# LCD_Controller.net
KiCad netlist of a schematic drawn in Altium Designer
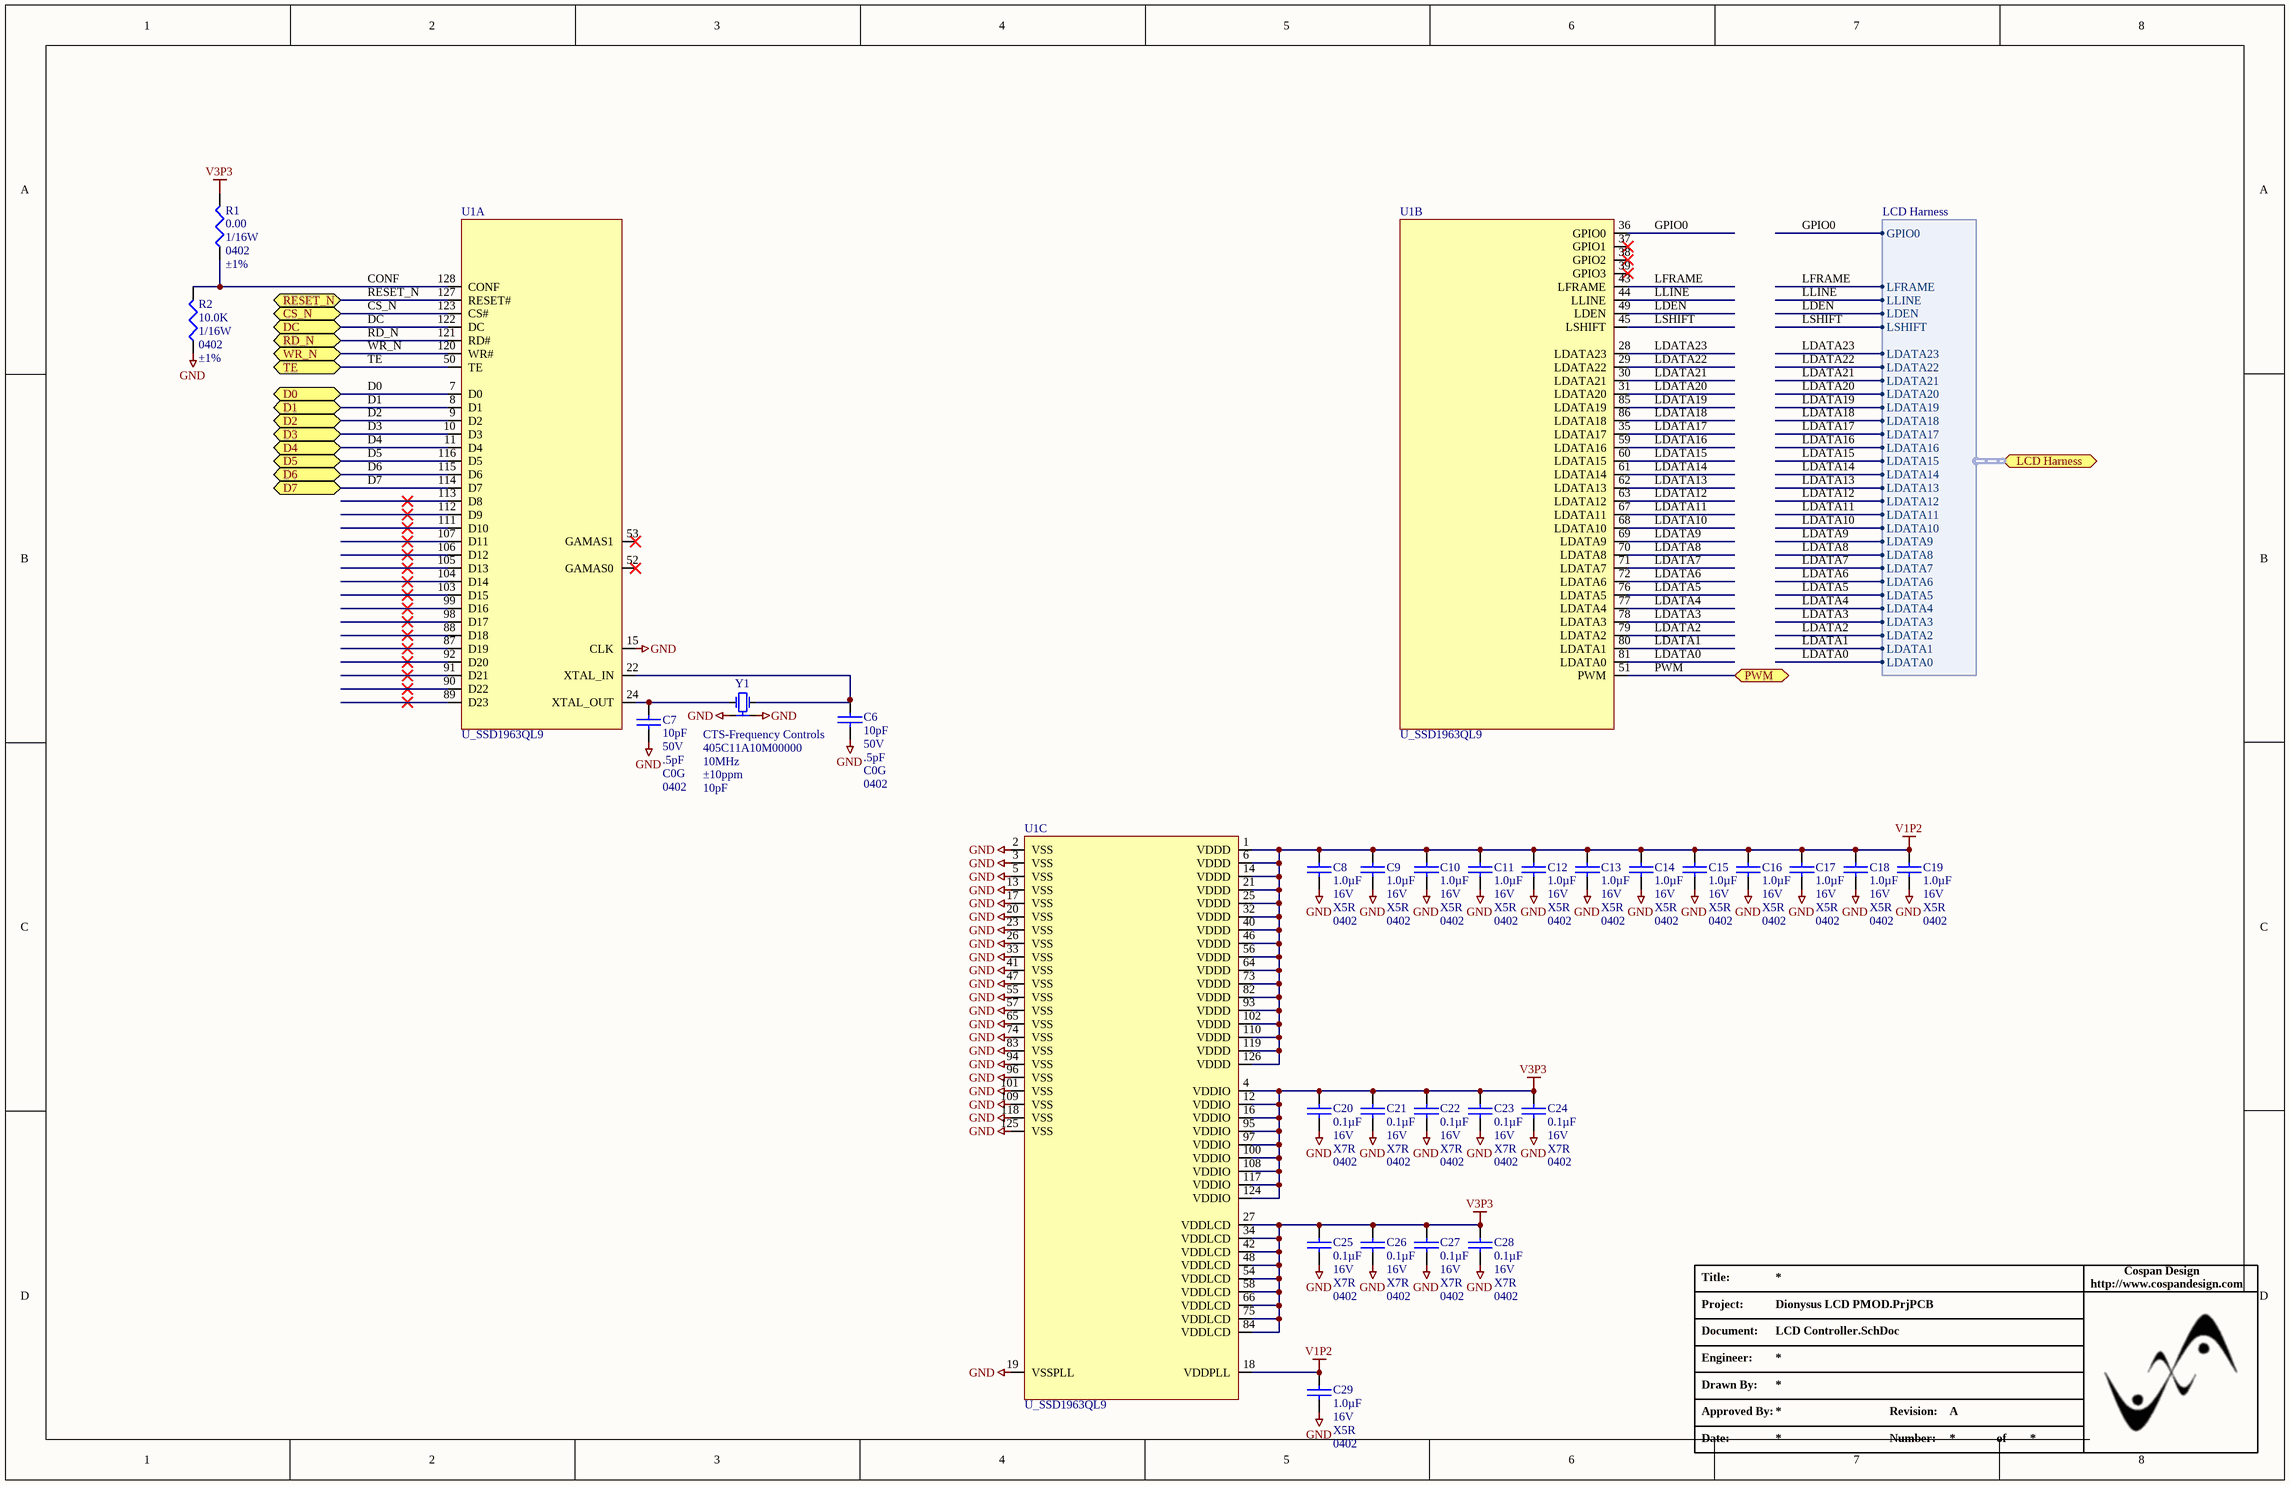
[diagram p0: LCD Controller.SchDoc]

(export (version "E")
  (design (tool "Eeschema 10.0.6"))
  (components
    (comp (ref "C6")
      (value "10pF")
      (footprint "C_ERA-0402")
      (description "CAP CER 10PF 50V NP0 0402")
      (fields
        (field (name "MANUFACTURER") "Taiyo Yuden")
        (field (name "MANUFACTURER PART NUMBER") "UMK105CG100DV-F")
        (field (name "CAPACITANCE") "10pF")
        (field (name "VOLTAGE - RATED") "50V")
        (field (name "TOLERANCE") ".5pF")
        (field (name "TEMPERATURE COEFFICIENT") "C0G")
        (field (name "PACKAGE / CASE") "0402")
      )
      (libsource (lib "Main Library") (part "C_0402_10PF_50V"))
    )
    (comp (ref "C7")
      (value "10pF")
      (footprint "C_ERA-0402")
      (description "CAP CER 10PF 50V NP0 0402")
      (fields
        (field (name "MANUFACTURER") "Taiyo Yuden")
        (field (name "MANUFACTURER PART NUMBER") "UMK105CG100DV-F")
        (field (name "CAPACITANCE") "10pF")
        (field (name "VOLTAGE - RATED") "50V")
        (field (name "TOLERANCE") ".5pF")
        (field (name "TEMPERATURE COEFFICIENT") "C0G")
        (field (name "PACKAGE / CASE") "0402")
      )
      (libsource (lib "Main Library") (part "C_0402_10PF_50V"))
    )
    (comp (ref "C8")
      (value "1.0uF")
      (footprint "C_ERA-0402")
      (description "CAP CER 1.0UF 16V X5R 0402")
      (fields
        (field (name "TOLERANCE") "±10%")
        (field (name "MANUFACTURER") "TDK Corporation")
        (field (name "CAPACITANCE") "1.0µF")
        (field (name "VOLTAGE - RATED") "16V")
        (field (name "TEMPERATURE COEFFICIENT") "X5R")
        (field (name "PACKAGE / CASE") "0402")
      )
      (libsource (lib "Main Library") (part "C_0402_1.0UF_16V"))
    )
    (comp (ref "C9")
      (value "1.0uF")
      (footprint "C_ERA-0402")
      (description "CAP CER 1.0UF 16V X5R 0402")
      (fields
        (field (name "TOLERANCE") "±10%")
        (field (name "MANUFACTURER") "TDK Corporation")
        (field (name "CAPACITANCE") "1.0µF")
        (field (name "VOLTAGE - RATED") "16V")
        (field (name "TEMPERATURE COEFFICIENT") "X5R")
        (field (name "PACKAGE / CASE") "0402")
      )
      (libsource (lib "Main Library") (part "C_0402_1.0UF_16V"))
    )
    (comp (ref "C10")
      (value "1.0uF")
      (footprint "C_ERA-0402")
      (description "CAP CER 1.0UF 16V X5R 0402")
      (fields
        (field (name "TOLERANCE") "±10%")
        (field (name "MANUFACTURER") "TDK Corporation")
        (field (name "CAPACITANCE") "1.0µF")
        (field (name "VOLTAGE - RATED") "16V")
        (field (name "TEMPERATURE COEFFICIENT") "X5R")
        (field (name "PACKAGE / CASE") "0402")
      )
      (libsource (lib "Main Library") (part "C_0402_1.0UF_16V"))
    )
    (comp (ref "C11")
      (value "1.0uF")
      (footprint "C_ERA-0402")
      (description "CAP CER 1.0UF 16V X5R 0402")
      (fields
        (field (name "TOLERANCE") "±10%")
        (field (name "MANUFACTURER") "TDK Corporation")
        (field (name "CAPACITANCE") "1.0µF")
        (field (name "VOLTAGE - RATED") "16V")
        (field (name "TEMPERATURE COEFFICIENT") "X5R")
        (field (name "PACKAGE / CASE") "0402")
      )
      (libsource (lib "Main Library") (part "C_0402_1.0UF_16V"))
    )
    (comp (ref "C12")
      (value "1.0uF")
      (footprint "C_ERA-0402")
      (description "CAP CER 1.0UF 16V X5R 0402")
      (fields
        (field (name "TOLERANCE") "±10%")
        (field (name "MANUFACTURER") "TDK Corporation")
        (field (name "CAPACITANCE") "1.0µF")
        (field (name "VOLTAGE - RATED") "16V")
        (field (name "TEMPERATURE COEFFICIENT") "X5R")
        (field (name "PACKAGE / CASE") "0402")
      )
      (libsource (lib "Main Library") (part "C_0402_1.0UF_16V"))
    )
    (comp (ref "C13")
      (value "1.0uF")
      (footprint "C_ERA-0402")
      (description "CAP CER 1.0UF 16V X5R 0402")
      (fields
        (field (name "TOLERANCE") "±10%")
        (field (name "MANUFACTURER") "TDK Corporation")
        (field (name "CAPACITANCE") "1.0µF")
        (field (name "VOLTAGE - RATED") "16V")
        (field (name "TEMPERATURE COEFFICIENT") "X5R")
        (field (name "PACKAGE / CASE") "0402")
      )
      (libsource (lib "Main Library") (part "C_0402_1.0UF_16V"))
    )
    (comp (ref "C14")
      (value "1.0uF")
      (footprint "C_ERA-0402")
      (description "CAP CER 1.0UF 16V X5R 0402")
      (fields
        (field (name "TOLERANCE") "±10%")
        (field (name "MANUFACTURER") "TDK Corporation")
        (field (name "CAPACITANCE") "1.0µF")
        (field (name "VOLTAGE - RATED") "16V")
        (field (name "TEMPERATURE COEFFICIENT") "X5R")
        (field (name "PACKAGE / CASE") "0402")
      )
      (libsource (lib "Main Library") (part "C_0402_1.0UF_16V"))
    )
    (comp (ref "C15")
      (value "1.0uF")
      (footprint "C_ERA-0402")
      (description "CAP CER 1.0UF 16V X5R 0402")
      (fields
        (field (name "TOLERANCE") "±10%")
        (field (name "MANUFACTURER") "TDK Corporation")
        (field (name "CAPACITANCE") "1.0µF")
        (field (name "VOLTAGE - RATED") "16V")
        (field (name "TEMPERATURE COEFFICIENT") "X5R")
        (field (name "PACKAGE / CASE") "0402")
      )
      (libsource (lib "Main Library") (part "C_0402_1.0UF_16V"))
    )
    (comp (ref "C16")
      (value "1.0uF")
      (footprint "C_ERA-0402")
      (description "CAP CER 1.0UF 16V X5R 0402")
      (fields
        (field (name "TOLERANCE") "±10%")
        (field (name "MANUFACTURER") "TDK Corporation")
        (field (name "CAPACITANCE") "1.0µF")
        (field (name "VOLTAGE - RATED") "16V")
        (field (name "TEMPERATURE COEFFICIENT") "X5R")
        (field (name "PACKAGE / CASE") "0402")
      )
      (libsource (lib "Main Library") (part "C_0402_1.0UF_16V"))
    )
    (comp (ref "C17")
      (value "1.0uF")
      (footprint "C_ERA-0402")
      (description "CAP CER 1.0UF 16V X5R 0402")
      (fields
        (field (name "TOLERANCE") "±10%")
        (field (name "MANUFACTURER") "TDK Corporation")
        (field (name "CAPACITANCE") "1.0µF")
        (field (name "VOLTAGE - RATED") "16V")
        (field (name "TEMPERATURE COEFFICIENT") "X5R")
        (field (name "PACKAGE / CASE") "0402")
      )
      (libsource (lib "Main Library") (part "C_0402_1.0UF_16V"))
    )
    (comp (ref "C18")
      (value "1.0uF")
      (footprint "C_ERA-0402")
      (description "CAP CER 1.0UF 16V X5R 0402")
      (fields
        (field (name "TOLERANCE") "±10%")
        (field (name "MANUFACTURER") "TDK Corporation")
        (field (name "CAPACITANCE") "1.0µF")
        (field (name "VOLTAGE - RATED") "16V")
        (field (name "TEMPERATURE COEFFICIENT") "X5R")
        (field (name "PACKAGE / CASE") "0402")
      )
      (libsource (lib "Main Library") (part "C_0402_1.0UF_16V"))
    )
    (comp (ref "C19")
      (value "1.0uF")
      (footprint "C_ERA-0402")
      (description "CAP CER 1.0UF 16V X5R 0402")
      (fields
        (field (name "TOLERANCE") "±10%")
        (field (name "MANUFACTURER") "TDK Corporation")
        (field (name "CAPACITANCE") "1.0µF")
        (field (name "VOLTAGE - RATED") "16V")
        (field (name "TEMPERATURE COEFFICIENT") "X5R")
        (field (name "PACKAGE / CASE") "0402")
      )
      (libsource (lib "Main Library") (part "C_0402_1.0UF_16V"))
    )
    (comp (ref "C20")
      (value "0.1uF")
      (footprint "C_0402")
      (description "CAP CER .10UF 16V X7R 0402")
      (fields
        (field (name "MANUFACTURER") "TDK Corporation")
        (field (name "MANUFACTURER PART NUMBER") "C1005X7R1C104K")
        (field (name "CAPACITANCE") "0.1µF")
        (field (name "VOLTAGE - RATED") "16V")
        (field (name "TEMPERATURE COEFFICIENT") "X7R")
        (field (name "PACKAGE / CASE") "0402")
      )
      (libsource (lib "Main Library") (part "C_0402_0.1UF_16V"))
    )
    (comp (ref "C21")
      (value "0.1uF")
      (footprint "C_0402")
      (description "CAP CER .10UF 16V X7R 0402")
      (fields
        (field (name "MANUFACTURER") "TDK Corporation")
        (field (name "MANUFACTURER PART NUMBER") "C1005X7R1C104K")
        (field (name "CAPACITANCE") "0.1µF")
        (field (name "VOLTAGE - RATED") "16V")
        (field (name "TEMPERATURE COEFFICIENT") "X7R")
        (field (name "PACKAGE / CASE") "0402")
      )
      (libsource (lib "Main Library") (part "C_0402_0.1UF_16V"))
    )
    (comp (ref "C22")
      (value "0.1uF")
      (footprint "C_0402")
      (description "CAP CER .10UF 16V X7R 0402")
      (fields
        (field (name "MANUFACTURER") "TDK Corporation")
        (field (name "MANUFACTURER PART NUMBER") "C1005X7R1C104K")
        (field (name "CAPACITANCE") "0.1µF")
        (field (name "VOLTAGE - RATED") "16V")
        (field (name "TEMPERATURE COEFFICIENT") "X7R")
        (field (name "PACKAGE / CASE") "0402")
      )
      (libsource (lib "Main Library") (part "C_0402_0.1UF_16V"))
    )
    (comp (ref "C23")
      (value "0.1uF")
      (footprint "C_0402")
      (description "CAP CER .10UF 16V X7R 0402")
      (fields
        (field (name "MANUFACTURER") "TDK Corporation")
        (field (name "MANUFACTURER PART NUMBER") "C1005X7R1C104K")
        (field (name "CAPACITANCE") "0.1µF")
        (field (name "VOLTAGE - RATED") "16V")
        (field (name "TEMPERATURE COEFFICIENT") "X7R")
        (field (name "PACKAGE / CASE") "0402")
      )
      (libsource (lib "Main Library") (part "C_0402_0.1UF_16V"))
    )
    (comp (ref "C24")
      (value "0.1uF")
      (footprint "C_0402")
      (description "CAP CER .10UF 16V X7R 0402")
      (fields
        (field (name "MANUFACTURER") "TDK Corporation")
        (field (name "MANUFACTURER PART NUMBER") "C1005X7R1C104K")
        (field (name "CAPACITANCE") "0.1µF")
        (field (name "VOLTAGE - RATED") "16V")
        (field (name "TEMPERATURE COEFFICIENT") "X7R")
        (field (name "PACKAGE / CASE") "0402")
      )
      (libsource (lib "Main Library") (part "C_0402_0.1UF_16V"))
    )
    (comp (ref "C25")
      (value "0.1uF")
      (footprint "C_0402")
      (description "CAP CER .10UF 16V X7R 0402")
      (fields
        (field (name "MANUFACTURER") "TDK Corporation")
        (field (name "MANUFACTURER PART NUMBER") "C1005X7R1C104K")
        (field (name "CAPACITANCE") "0.1µF")
        (field (name "VOLTAGE - RATED") "16V")
        (field (name "TEMPERATURE COEFFICIENT") "X7R")
        (field (name "PACKAGE / CASE") "0402")
      )
      (libsource (lib "Main Library") (part "C_0402_0.1UF_16V"))
    )
    (comp (ref "C26")
      (value "0.1uF")
      (footprint "C_0402")
      (description "CAP CER .10UF 16V X7R 0402")
      (fields
        (field (name "MANUFACTURER") "TDK Corporation")
        (field (name "MANUFACTURER PART NUMBER") "C1005X7R1C104K")
        (field (name "CAPACITANCE") "0.1µF")
        (field (name "VOLTAGE - RATED") "16V")
        (field (name "TEMPERATURE COEFFICIENT") "X7R")
        (field (name "PACKAGE / CASE") "0402")
      )
      (libsource (lib "Main Library") (part "C_0402_0.1UF_16V"))
    )
    (comp (ref "C27")
      (value "0.1uF")
      (footprint "C_0402")
      (description "CAP CER .10UF 16V X7R 0402")
      (fields
        (field (name "MANUFACTURER") "TDK Corporation")
        (field (name "MANUFACTURER PART NUMBER") "C1005X7R1C104K")
        (field (name "CAPACITANCE") "0.1µF")
        (field (name "VOLTAGE - RATED") "16V")
        (field (name "TEMPERATURE COEFFICIENT") "X7R")
        (field (name "PACKAGE / CASE") "0402")
      )
      (libsource (lib "Main Library") (part "C_0402_0.1UF_16V"))
    )
    (comp (ref "C28")
      (value "0.1uF")
      (footprint "C_0402")
      (description "CAP CER .10UF 16V X7R 0402")
      (fields
        (field (name "MANUFACTURER") "TDK Corporation")
        (field (name "MANUFACTURER PART NUMBER") "C1005X7R1C104K")
        (field (name "CAPACITANCE") "0.1µF")
        (field (name "VOLTAGE - RATED") "16V")
        (field (name "TEMPERATURE COEFFICIENT") "X7R")
        (field (name "PACKAGE / CASE") "0402")
      )
      (libsource (lib "Main Library") (part "C_0402_0.1UF_16V"))
    )
    (comp (ref "C29")
      (value "1.0uF")
      (footprint "C_ERA-0402")
      (description "CAP CER 1.0UF 16V X5R 0402")
      (fields
        (field (name "TOLERANCE") "±10%")
        (field (name "MANUFACTURER") "TDK Corporation")
        (field (name "CAPACITANCE") "1.0µF")
        (field (name "VOLTAGE - RATED") "16V")
        (field (name "TEMPERATURE COEFFICIENT") "X5R")
        (field (name "PACKAGE / CASE") "0402")
      )
      (libsource (lib "Main Library") (part "C_0402_1.0UF_16V"))
    )
    (comp (ref "R1")
      (value "0.0 Ohms")
      (footprint "R_0402")
      (description "RES 1.00 OHM 1/16W 1% 0402 SMD")
      (fields
        (field (name "MANUFACTURER") "Panasonic - ECG")
        (field (name "MANUFACTURER PART NUMBER") "ERJ-2GE0R00X")
        (field (name "RESISTANCE IN OHMS") "0.00")
        (field (name "POWER (WATTS)") "1/16W")
        (field (name "CASE") "0402")
        (field (name "TOLERANCE") "±1%")
      )
      (libsource (lib "Main Library") (part "R_0402_0.00"))
    )
    (comp (ref "R2")
      (value "R_0402_10.0K")
      (footprint "R_0402")
      (description "RES 10.0K OHM 1/16W 1% 0402 SMD")
      (fields
        (field (name "MANUFACTURER") "Stackpole Electronics Inc")
        (field (name "MANUFACTURER PART NUMBER") "RMCF0402FT10K0")
        (field (name "RESISTANCE IN OHMS") "10.0K")
        (field (name "POWER (WATTS)") "1/16W")
        (field (name "CASE") "0402")
        (field (name "TOLERANCE") "±1%")
      )
      (libsource (lib "Main Library") (part "R_0402_10.0K"))
    )
    (comp (ref "U1")
      (value "U_SSD1963QL9")
      (footprint "LQFP128")
      (description "SSD1963QL9")
      (libsource (lib "Main LibraryX") (part "U_SSD1963QL9"))
    )
    (comp (ref "Y1")
      (value "Y_SMD_10.00MHZ_10PF")
      (footprint "SMD_OSC_8MHZ")
      (description "CRYSTAL 10MHZ 10PF SMD")
      (fields
        (field (name "MANUFACTURER") "CTS-Frequency Controls")
        (field (name "MANUFACTURER PART NUMBER") "405C11A10M00000")
        (field (name "FREQUENCY") "10MHz")
        (field (name "FREQUENCY STABILITY") "±10ppm")
        (field (name "LOAD CAPACITANCE") "10pF")
      )
      (libsource (lib "Main Library") (part "Y_SMD_10.00MHZ_10PF"))
    )
  )
  (nets
    (net (code "3") (name "/CONF") (class "Default")
      (node (ref "R1") (pin "2") (pinfunction "2_2") (pintype "passive"))
      (node (ref "R2") (pin "1") (pinfunction "1_1") (pintype "passive"))
      (node (ref "U1") (pin "128") (pinfunction "CONF_128") (pintype "passive"))
    )
    (net (code "4") (name "/CS_N") (class "Default")
      (node (ref "U1") (pin "123") (pinfunction "CS#_123") (pintype "passive"))
    )
    (net (code "5") (name "/D0") (class "Default")
      (node (ref "U1") (pin "7") (pinfunction "D0_7") (pintype "passive"))
    )
    (net (code "6") (name "/D1") (class "Default")
      (node (ref "U1") (pin "8") (pinfunction "D1_8") (pintype "passive"))
    )
    (net (code "7") (name "/D2") (class "Default")
      (node (ref "U1") (pin "9") (pinfunction "D2_9") (pintype "passive"))
    )
    (net (code "8") (name "/D3") (class "Default")
      (node (ref "U1") (pin "10") (pinfunction "D3_10") (pintype "passive"))
    )
    (net (code "9") (name "/D4") (class "Default")
      (node (ref "U1") (pin "11") (pinfunction "D4_11") (pintype "passive"))
    )
    (net (code "10") (name "/D5") (class "Default")
      (node (ref "U1") (pin "116") (pinfunction "D5_116") (pintype "passive"))
    )
    (net (code "11") (name "/D6") (class "Default")
      (node (ref "U1") (pin "115") (pinfunction "D6_115") (pintype "passive"))
    )
    (net (code "12") (name "/D7") (class "Default")
      (node (ref "U1") (pin "114") (pinfunction "D7_114") (pintype "passive"))
    )
    (net (code "13") (name "/DC") (class "Default")
      (node (ref "U1") (pin "122") (pinfunction "DC_122") (pintype "passive"))
    )
    (net (code "14") (name "/GPIO0") (class "Default")
      (node (ref "U1") (pin "36") (pinfunction "GPIO0_36") (pintype "passive"))
    )
    (net (code "15") (name "/LDATA0") (class "Default")
      (node (ref "U1") (pin "81") (pinfunction "LDATA0_81") (pintype "passive"))
    )
    (net (code "16") (name "/LDATA1") (class "Default")
      (node (ref "U1") (pin "80") (pinfunction "LDATA1_80") (pintype "passive"))
    )
    (net (code "17") (name "/LDATA2") (class "Default")
      (node (ref "U1") (pin "79") (pinfunction "LDATA2_79") (pintype "passive"))
    )
    (net (code "18") (name "/LDATA3") (class "Default")
      (node (ref "U1") (pin "78") (pinfunction "LDATA3_78") (pintype "passive"))
    )
    (net (code "19") (name "/LDATA4") (class "Default")
      (node (ref "U1") (pin "77") (pinfunction "LDATA4_77") (pintype "passive"))
    )
    (net (code "20") (name "/LDATA5") (class "Default")
      (node (ref "U1") (pin "76") (pinfunction "LDATA5_76") (pintype "passive"))
    )
    (net (code "21") (name "/LDATA6") (class "Default")
      (node (ref "U1") (pin "72") (pinfunction "LDATA6_72") (pintype "passive"))
    )
    (net (code "22") (name "/LDATA7") (class "Default")
      (node (ref "U1") (pin "71") (pinfunction "LDATA7_71") (pintype "passive"))
    )
    (net (code "23") (name "/LDATA8") (class "Default")
      (node (ref "U1") (pin "70") (pinfunction "LDATA8_70") (pintype "passive"))
    )
    (net (code "24") (name "/LDATA9") (class "Default")
      (node (ref "U1") (pin "69") (pinfunction "LDATA9_69") (pintype "passive"))
    )
    (net (code "25") (name "/LDATA10") (class "Default")
      (node (ref "U1") (pin "68") (pinfunction "LDATA10_68") (pintype "passive"))
    )
    (net (code "26") (name "/LDATA11") (class "Default")
      (node (ref "U1") (pin "67") (pinfunction "LDATA11_67") (pintype "passive"))
    )
    (net (code "27") (name "/LDATA12") (class "Default")
      (node (ref "U1") (pin "63") (pinfunction "LDATA12_63") (pintype "passive"))
    )
    (net (code "28") (name "/LDATA13") (class "Default")
      (node (ref "U1") (pin "62") (pinfunction "LDATA13_62") (pintype "passive"))
    )
    (net (code "29") (name "/LDATA14") (class "Default")
      (node (ref "U1") (pin "61") (pinfunction "LDATA14_61") (pintype "passive"))
    )
    (net (code "30") (name "/LDATA15") (class "Default")
      (node (ref "U1") (pin "60") (pinfunction "LDATA15_60") (pintype "passive"))
    )
    (net (code "31") (name "/LDATA16") (class "Default")
      (node (ref "U1") (pin "59") (pinfunction "LDATA16_59") (pintype "passive"))
    )
    (net (code "32") (name "/LDATA17") (class "Default")
      (node (ref "U1") (pin "35") (pinfunction "LDATA17_35") (pintype "passive"))
    )
    (net (code "33") (name "/LDATA18") (class "Default")
      (node (ref "U1") (pin "86") (pinfunction "LDATA18_86") (pintype "passive"))
    )
    (net (code "34") (name "/LDATA19") (class "Default")
      (node (ref "U1") (pin "85") (pinfunction "LDATA19_85") (pintype "passive"))
    )
    (net (code "35") (name "/LDATA20") (class "Default")
      (node (ref "U1") (pin "31") (pinfunction "LDATA20_31") (pintype "passive"))
    )
    (net (code "36") (name "/LDATA21") (class "Default")
      (node (ref "U1") (pin "30") (pinfunction "LDATA21_30") (pintype "passive"))
    )
    (net (code "37") (name "/LDATA22") (class "Default")
      (node (ref "U1") (pin "29") (pinfunction "LDATA22_29") (pintype "passive"))
    )
    (net (code "38") (name "/LDATA23") (class "Default")
      (node (ref "U1") (pin "28") (pinfunction "LDATA23_28") (pintype "passive"))
    )
    (net (code "39") (name "/LDEN") (class "Default")
      (node (ref "U1") (pin "49") (pinfunction "LDEN_49") (pintype "passive"))
    )
    (net (code "40") (name "/LFRAME") (class "Default")
      (node (ref "U1") (pin "43") (pinfunction "LFRAME_43") (pintype "passive"))
    )
    (net (code "41") (name "/LLINE") (class "Default")
      (node (ref "U1") (pin "44") (pinfunction "LLINE_44") (pintype "passive"))
    )
    (net (code "42") (name "/LSHIFT") (class "Default")
      (node (ref "U1") (pin "45") (pinfunction "LSHIFT_45") (pintype "passive"))
    )
    (net (code "43") (name "/PWM") (class "Default")
      (node (ref "U1") (pin "51") (pinfunction "PWM_51") (pintype "passive"))
    )
    (net (code "44") (name "/RD_N") (class "Default")
      (node (ref "U1") (pin "121") (pinfunction "RD#_121") (pintype "passive"))
    )
    (net (code "45") (name "/RESET_N") (class "Default")
      (node (ref "U1") (pin "127") (pinfunction "RESET#_127") (pintype "passive"))
    )
    (net (code "46") (name "/TE") (class "Default")
      (node (ref "U1") (pin "50") (pinfunction "TE_50") (pintype "passive"))
    )
    (net (code "47") (name "/WR_N") (class "Default")
      (node (ref "U1") (pin "120") (pinfunction "WR#_120") (pintype "passive"))
    )
    (net (code "49") (name "GND") (class "Default")
      (node (ref "C10") (pin "1") (pinfunction "1_1") (pintype "passive"))
      (node (ref "C11") (pin "1") (pinfunction "1_1") (pintype "passive"))
      (node (ref "C12") (pin "1") (pinfunction "1_1") (pintype "passive"))
      (node (ref "C13") (pin "1") (pinfunction "1_1") (pintype "passive"))
      (node (ref "C14") (pin "1") (pinfunction "1_1") (pintype "passive"))
      (node (ref "C15") (pin "1") (pinfunction "1_1") (pintype "passive"))
      (node (ref "C16") (pin "1") (pinfunction "1_1") (pintype "passive"))
      (node (ref "C17") (pin "1") (pinfunction "1_1") (pintype "passive"))
      (node (ref "C18") (pin "1") (pinfunction "1_1") (pintype "passive"))
      (node (ref "C19") (pin "1") (pinfunction "1_1") (pintype "passive"))
      (node (ref "C20") (pin "1") (pinfunction "1_1") (pintype "passive"))
      (node (ref "C21") (pin "1") (pinfunction "1_1") (pintype "passive"))
      (node (ref "C22") (pin "1") (pinfunction "1_1") (pintype "passive"))
      (node (ref "C23") (pin "1") (pinfunction "1_1") (pintype "passive"))
      (node (ref "C24") (pin "1") (pinfunction "1_1") (pintype "passive"))
      (node (ref "C25") (pin "1") (pinfunction "1_1") (pintype "passive"))
      (node (ref "C26") (pin "1") (pinfunction "1_1") (pintype "passive"))
      (node (ref "C27") (pin "1") (pinfunction "1_1") (pintype "passive"))
      (node (ref "C28") (pin "1") (pinfunction "1_1") (pintype "passive"))
      (node (ref "C29") (pin "1") (pinfunction "1_1") (pintype "passive"))
      (node (ref "C6") (pin "1") (pinfunction "1_1") (pintype "passive"))
      (node (ref "C7") (pin "1") (pinfunction "1_1") (pintype "passive"))
      (node (ref "C8") (pin "1") (pinfunction "1_1") (pintype "passive"))
      (node (ref "C9") (pin "1") (pinfunction "1_1") (pintype "passive"))
      (node (ref "R2") (pin "2") (pinfunction "2_2") (pintype "passive"))
      (node (ref "U1") (pin "101") (pinfunction "VSS_101") (pintype "passive"))
      (node (ref "U1") (pin "109") (pinfunction "VSS_109") (pintype "passive"))
      (node (ref "U1") (pin "118") (pinfunction "VSS_118") (pintype "passive"))
      (node (ref "U1") (pin "125") (pinfunction "VSS_125") (pintype "passive"))
      (node (ref "U1") (pin "13") (pinfunction "VSS_13") (pintype "passive"))
      (node (ref "U1") (pin "15") (pinfunction "CLK_15") (pintype "passive"))
      (node (ref "U1") (pin "17") (pinfunction "VSS_17") (pintype "passive"))
      (node (ref "U1") (pin "19") (pinfunction "VSSPLL_19") (pintype "passive"))
      (node (ref "U1") (pin "2") (pinfunction "VSS_2") (pintype "passive"))
      (node (ref "U1") (pin "20") (pinfunction "VSS_20") (pintype "passive"))
      (node (ref "U1") (pin "23") (pinfunction "VSS_23") (pintype "passive"))
      (node (ref "U1") (pin "26") (pinfunction "VSS_26") (pintype "passive"))
      (node (ref "U1") (pin "3") (pinfunction "VSS_3") (pintype "passive"))
      (node (ref "U1") (pin "33") (pinfunction "VSS_33") (pintype "passive"))
      (node (ref "U1") (pin "41") (pinfunction "VSS_41") (pintype "passive"))
      (node (ref "U1") (pin "47") (pinfunction "VSS_47") (pintype "passive"))
      (node (ref "U1") (pin "5") (pinfunction "VSS_5") (pintype "passive"))
      (node (ref "U1") (pin "55") (pinfunction "VSS_55") (pintype "passive"))
      (node (ref "U1") (pin "57") (pinfunction "VSS_57") (pintype "passive"))
      (node (ref "U1") (pin "65") (pinfunction "VSS_65") (pintype "passive"))
      (node (ref "U1") (pin "74") (pinfunction "VSS_74") (pintype "passive"))
      (node (ref "U1") (pin "83") (pinfunction "VSS_83") (pintype "passive"))
      (node (ref "U1") (pin "94") (pinfunction "VSS_94") (pintype "passive"))
      (node (ref "U1") (pin "96") (pinfunction "VSS_96") (pintype "passive"))
      (node (ref "Y1") (pin "2") (pinfunction "2_2") (pintype "passive"))
      (node (ref "Y1") (pin "4") (pinfunction "4_4") (pintype "passive"))
    )
    (net (code "50") (name "Net-(U1A-XTAL_IN)") (class "Default")
      (node (ref "C6") (pin "2") (pinfunction "2_2") (pintype "passive"))
      (node (ref "U1") (pin "22") (pinfunction "XTAL_IN_22") (pintype "passive"))
      (node (ref "Y1") (pin "3") (pinfunction "3_3") (pintype "passive"))
    )
    (net (code "51") (name "Net-(U1A-XTAL_OUT)") (class "Default")
      (node (ref "C7") (pin "2") (pinfunction "2_2") (pintype "passive"))
      (node (ref "U1") (pin "24") (pinfunction "XTAL_OUT_24") (pintype "passive"))
      (node (ref "Y1") (pin "1") (pinfunction "1_1") (pintype "passive"))
    )
    (net (code "52") (name "V1P2") (class "Default")
      (node (ref "C10") (pin "2") (pinfunction "2_2") (pintype "passive"))
      (node (ref "C11") (pin "2") (pinfunction "2_2") (pintype "passive"))
      (node (ref "C12") (pin "2") (pinfunction "2_2") (pintype "passive"))
      (node (ref "C13") (pin "2") (pinfunction "2_2") (pintype "passive"))
      (node (ref "C14") (pin "2") (pinfunction "2_2") (pintype "passive"))
      (node (ref "C15") (pin "2") (pinfunction "2_2") (pintype "passive"))
      (node (ref "C16") (pin "2") (pinfunction "2_2") (pintype "passive"))
      (node (ref "C17") (pin "2") (pinfunction "2_2") (pintype "passive"))
      (node (ref "C18") (pin "2") (pinfunction "2_2") (pintype "passive"))
      (node (ref "C19") (pin "2") (pinfunction "2_2") (pintype "passive"))
      (node (ref "C29") (pin "2") (pinfunction "2_2") (pintype "passive"))
      (node (ref "C8") (pin "2") (pinfunction "2_2") (pintype "passive"))
      (node (ref "C9") (pin "2") (pinfunction "2_2") (pintype "passive"))
      (node (ref "U1") (pin "1") (pinfunction "VDDD_1") (pintype "passive"))
      (node (ref "U1") (pin "102") (pinfunction "VDDD_102") (pintype "passive"))
      (node (ref "U1") (pin "110") (pinfunction "VDDD_110") (pintype "passive"))
      (node (ref "U1") (pin "119") (pinfunction "VDDD_119") (pintype "passive"))
      (node (ref "U1") (pin "126") (pinfunction "VDDD_126") (pintype "passive"))
      (node (ref "U1") (pin "14") (pinfunction "VDDD_14") (pintype "passive"))
      (node (ref "U1") (pin "18") (pinfunction "VDDPLL_18") (pintype "passive"))
      (node (ref "U1") (pin "21") (pinfunction "VDDD_21") (pintype "passive"))
      (node (ref "U1") (pin "25") (pinfunction "VDDD_25") (pintype "passive"))
      (node (ref "U1") (pin "32") (pinfunction "VDDD_32") (pintype "passive"))
      (node (ref "U1") (pin "40") (pinfunction "VDDD_40") (pintype "passive"))
      (node (ref "U1") (pin "46") (pinfunction "VDDD_46") (pintype "passive"))
      (node (ref "U1") (pin "56") (pinfunction "VDDD_56") (pintype "passive"))
      (node (ref "U1") (pin "6") (pinfunction "VDDD_6") (pintype "passive"))
      (node (ref "U1") (pin "64") (pinfunction "VDDD_64") (pintype "passive"))
      (node (ref "U1") (pin "73") (pinfunction "VDDD_73") (pintype "passive"))
      (node (ref "U1") (pin "82") (pinfunction "VDDD_82") (pintype "passive"))
      (node (ref "U1") (pin "93") (pinfunction "VDDD_93") (pintype "passive"))
    )
    (net (code "53") (name "V3P3") (class "Default")
      (node (ref "C20") (pin "2") (pinfunction "2_2") (pintype "passive"))
      (node (ref "C21") (pin "2") (pinfunction "2_2") (pintype "passive"))
      (node (ref "C22") (pin "2") (pinfunction "2_2") (pintype "passive"))
      (node (ref "C23") (pin "2") (pinfunction "2_2") (pintype "passive"))
      (node (ref "C24") (pin "2") (pinfunction "2_2") (pintype "passive"))
      (node (ref "C25") (pin "2") (pinfunction "2_2") (pintype "passive"))
      (node (ref "C26") (pin "2") (pinfunction "2_2") (pintype "passive"))
      (node (ref "C27") (pin "2") (pinfunction "2_2") (pintype "passive"))
      (node (ref "C28") (pin "2") (pinfunction "2_2") (pintype "passive"))
      (node (ref "R1") (pin "1") (pinfunction "1_1") (pintype "passive"))
      (node (ref "U1") (pin "100") (pinfunction "VDDIO_100") (pintype "passive"))
      (node (ref "U1") (pin "108") (pinfunction "VDDIO_108") (pintype "passive"))
      (node (ref "U1") (pin "117") (pinfunction "VDDIO_117") (pintype "passive"))
      (node (ref "U1") (pin "12") (pinfunction "VDDIO_12") (pintype "passive"))
      (node (ref "U1") (pin "124") (pinfunction "VDDIO_124") (pintype "passive"))
      (node (ref "U1") (pin "16") (pinfunction "VDDIO_16") (pintype "passive"))
      (node (ref "U1") (pin "27") (pinfunction "VDDLCD_27") (pintype "passive"))
      (node (ref "U1") (pin "34") (pinfunction "VDDLCD_34") (pintype "passive"))
      (node (ref "U1") (pin "4") (pinfunction "VDDIO_4") (pintype "passive"))
      (node (ref "U1") (pin "42") (pinfunction "VDDLCD_42") (pintype "passive"))
      (node (ref "U1") (pin "48") (pinfunction "VDDLCD_48") (pintype "passive"))
      (node (ref "U1") (pin "54") (pinfunction "VDDLCD_54") (pintype "passive"))
      (node (ref "U1") (pin "58") (pinfunction "VDDLCD_58") (pintype "passive"))
      (node (ref "U1") (pin "66") (pinfunction "VDDLCD_66") (pintype "passive"))
      (node (ref "U1") (pin "75") (pinfunction "VDDLCD_75") (pintype "passive"))
      (node (ref "U1") (pin "84") (pinfunction "VDDLCD_84") (pintype "passive"))
      (node (ref "U1") (pin "95") (pinfunction "VDDIO_95") (pintype "passive"))
      (node (ref "U1") (pin "97") (pinfunction "VDDIO_97") (pintype "passive"))
    )
    (net (code "54") (name "unconnected-(U1A-D8-Pad113)") (class "Default")
      (node (ref "U1") (pin "113") (pinfunction "D8_113") (pintype "passive+no_connect"))
    )
    (net (code "55") (name "unconnected-(U1A-D9-Pad112)") (class "Default")
      (node (ref "U1") (pin "112") (pinfunction "D9_112") (pintype "passive+no_connect"))
    )
    (net (code "56") (name "unconnected-(U1A-D10-Pad111)") (class "Default")
      (node (ref "U1") (pin "111") (pinfunction "D10_111") (pintype "passive+no_connect"))
    )
    (net (code "57") (name "unconnected-(U1A-D11-Pad107)") (class "Default")
      (node (ref "U1") (pin "107") (pinfunction "D11_107") (pintype "passive+no_connect"))
    )
    (net (code "58") (name "unconnected-(U1A-D12-Pad106)") (class "Default")
      (node (ref "U1") (pin "106") (pinfunction "D12_106") (pintype "passive+no_connect"))
    )
    (net (code "59") (name "unconnected-(U1A-D13-Pad105)") (class "Default")
      (node (ref "U1") (pin "105") (pinfunction "D13_105") (pintype "passive+no_connect"))
    )
    (net (code "60") (name "unconnected-(U1A-D14-Pad104)") (class "Default")
      (node (ref "U1") (pin "104") (pinfunction "D14_104") (pintype "passive+no_connect"))
    )
    (net (code "61") (name "unconnected-(U1A-D15-Pad103)") (class "Default")
      (node (ref "U1") (pin "103") (pinfunction "D15_103") (pintype "passive+no_connect"))
    )
    (net (code "62") (name "unconnected-(U1A-D16-Pad99)") (class "Default")
      (node (ref "U1") (pin "99") (pinfunction "D16_99") (pintype "passive+no_connect"))
    )
    (net (code "63") (name "unconnected-(U1A-D17-Pad98)") (class "Default")
      (node (ref "U1") (pin "98") (pinfunction "D17_98") (pintype "passive+no_connect"))
    )
    (net (code "64") (name "unconnected-(U1A-D18-Pad88)") (class "Default")
      (node (ref "U1") (pin "88") (pinfunction "D18_88") (pintype "passive+no_connect"))
    )
    (net (code "65") (name "unconnected-(U1A-D19-Pad87)") (class "Default")
      (node (ref "U1") (pin "87") (pinfunction "D19_87") (pintype "passive+no_connect"))
    )
    (net (code "66") (name "unconnected-(U1A-D20-Pad92)") (class "Default")
      (node (ref "U1") (pin "92") (pinfunction "D20_92") (pintype "passive+no_connect"))
    )
    (net (code "67") (name "unconnected-(U1A-D21-Pad91)") (class "Default")
      (node (ref "U1") (pin "91") (pinfunction "D21_91") (pintype "passive+no_connect"))
    )
    (net (code "68") (name "unconnected-(U1A-D22-Pad90)") (class "Default")
      (node (ref "U1") (pin "90") (pinfunction "D22_90") (pintype "passive+no_connect"))
    )
    (net (code "69") (name "unconnected-(U1A-D23-Pad89)") (class "Default")
      (node (ref "U1") (pin "89") (pinfunction "D23_89") (pintype "passive+no_connect"))
    )
    (net (code "70") (name "unconnected-(U1A-GAMAS0-Pad52)") (class "Default")
      (node (ref "U1") (pin "52") (pinfunction "GAMAS0_52") (pintype "passive+no_connect"))
    )
    (net (code "71") (name "unconnected-(U1A-GAMAS1-Pad53)") (class "Default")
      (node (ref "U1") (pin "53") (pinfunction "GAMAS1_53") (pintype "passive+no_connect"))
    )
    (net (code "72") (name "unconnected-(U1B-GPIO1-Pad37)") (class "Default")
      (node (ref "U1") (pin "37") (pinfunction "GPIO1_37") (pintype "passive+no_connect"))
    )
    (net (code "73") (name "unconnected-(U1B-GPIO2-Pad38)") (class "Default")
      (node (ref "U1") (pin "38") (pinfunction "GPIO2_38") (pintype "passive+no_connect"))
    )
    (net (code "74") (name "unconnected-(U1B-GPIO3-Pad39)") (class "Default")
      (node (ref "U1") (pin "39") (pinfunction "GPIO3_39") (pintype "passive+no_connect"))
    )
  )
)
